# v2.net
KiCad netlist of a schematic drawn in EAGLE
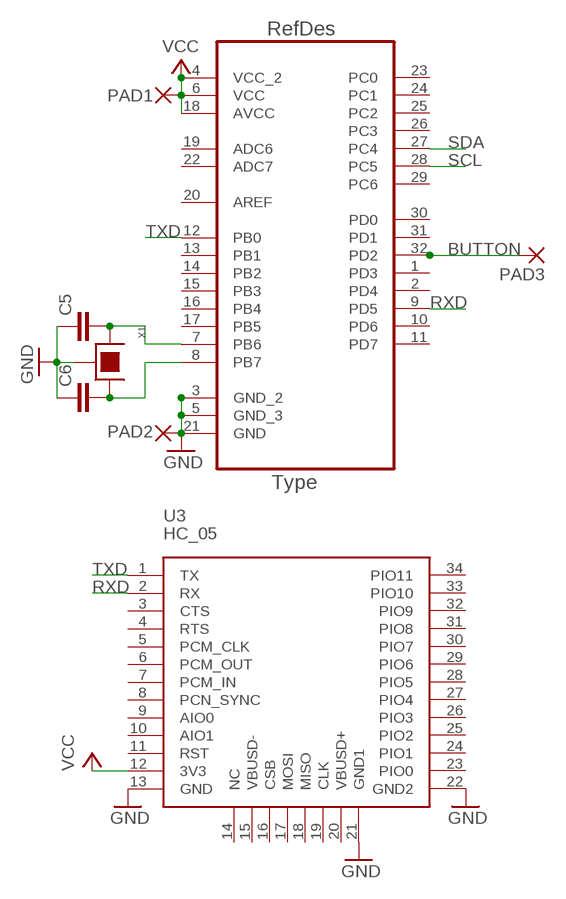
[diagram p0: schematic, sheet 1]
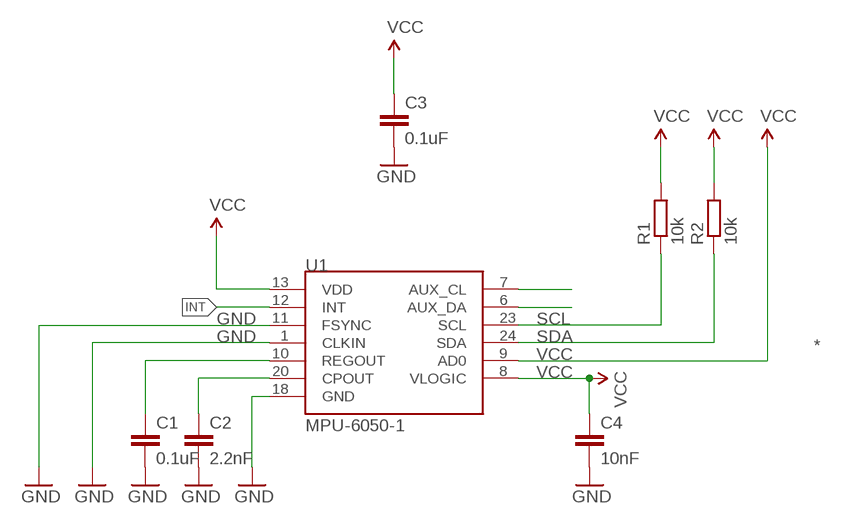
[diagram p1: schematic, sheet 2]

(export (version "E")
  (design (tool "Eeschema 10.0.6"))
  (components
    (comp (ref "C5")
      (value "C-EUC0402")
      (footprint "eagle-import:C0402")
      (libsource (lib "eagle-import") (part "C-EUC0402"))
    )
    (comp (ref "C6")
      (value "C-EUC0402")
      (footprint "eagle-import:C0402")
      (libsource (lib "eagle-import") (part "C-EUC0402"))
    )
    (comp (ref "PAD1")
      (value "SMD2")
      (footprint "eagle-import:SMD1,27-2,54")
      (libsource (lib "eagle-import") (part "SMD2"))
    )
    (comp (ref "PAD2")
      (value "SMD2")
      (footprint "eagle-import:SMD1,27-2,54")
      (libsource (lib "eagle-import") (part "SMD2"))
    )
    (comp (ref "PAD3")
      (value "SMD2")
      (footprint "eagle-import:SMD1,27-2,54")
      (libsource (lib "eagle-import") (part "SMD2"))
    )
    (comp (ref "U2")
      (value "ATMEGA328P-AU")
      (footprint "eagle-import:QFP80P900X900X120-32N")
      (libsource (lib "eagle-import") (part "ATMEGA328P-AU"))
    )
    (comp (ref "U3")
      (value "HC_05")
      (footprint "eagle-import:BLUETOOTH_SMD")
      (libsource (lib "eagle-import") (part "HC_05"))
    )
    (comp (ref "X1")
      (value "SHIELDED_CRYSTAL_TSX-3225")
      (footprint "eagle-import:TSX-3225")
      (libsource (lib "eagle-import") (part "SHIELDED_CRYSTAL_TSX-3225"))
    )
    (comp (ref "C1")
      (value "0.1uF")
      (footprint "eagle-import:C0402")
      (libsource (lib "eagle-import") (part "C-EUC0402"))
    )
    (comp (ref "C2")
      (value "2.2nF")
      (footprint "eagle-import:C0402")
      (libsource (lib "eagle-import") (part "C-EUC0402"))
    )
    (comp (ref "C3")
      (value "0.1uF")
      (footprint "eagle-import:C0402")
      (libsource (lib "eagle-import") (part "C-EUC0402"))
    )
    (comp (ref "C4")
      (value "10nF")
      (footprint "eagle-import:C0402")
      (libsource (lib "eagle-import") (part "C-EUC0402"))
    )
    (comp (ref "R1")
      (value "10k")
      (footprint "eagle-import:R0402")
      (libsource (lib "eagle-import") (part "R-EU_R0402"))
    )
    (comp (ref "R2")
      (value "10k")
      (footprint "eagle-import:R0402")
      (libsource (lib "eagle-import") (part "R-EU_R0402"))
    )
    (comp (ref "U1")
      (value "MPU-6050-1")
      (footprint "eagle-import:QFN-24-4MM2")
      (libsource (lib "eagle-import") (part "MPU-6050-1"))
    )
  )
  (nets
    (net (code "1") (name "BUTTON") (class "Default")
      (node (ref "PAD3") (pin "1") (pinfunction "P_1") (pintype "passive"))
      (node (ref "U2") (pin "32") (pinfunction "PD2_32") (pintype "bidirectional"))
    )
    (net (code "2") (name "GND") (class "Default")
      (node (ref "C1") (pin "2") (pinfunction "2_2") (pintype "passive"))
      (node (ref "C2") (pin "2") (pinfunction "2_2") (pintype "passive"))
      (node (ref "C3") (pin "2") (pinfunction "2_2") (pintype "passive"))
      (node (ref "C4") (pin "2") (pinfunction "2_2") (pintype "passive"))
      (node (ref "C5") (pin "1") (pinfunction "1_1") (pintype "passive"))
      (node (ref "C6") (pin "1") (pinfunction "1_1") (pintype "passive"))
      (node (ref "PAD2") (pin "1") (pinfunction "P_1") (pintype "passive"))
      (node (ref "U1") (pin "1") (pinfunction "CLKIN_1") (pintype "bidirectional"))
      (node (ref "U1") (pin "11") (pinfunction "FSYNC_11") (pintype "bidirectional"))
      (node (ref "U1") (pin "18") (pinfunction "GND_18") (pintype "bidirectional"))
      (node (ref "U2") (pin "21") (pinfunction "GND_21") (pintype "passive"))
      (node (ref "U2") (pin "3") (pinfunction "GND_2_3") (pintype "passive"))
      (node (ref "U2") (pin "5") (pinfunction "GND_3_5") (pintype "passive"))
      (node (ref "U3") (pin "13") (pinfunction "GND_13") (pintype "bidirectional"))
      (node (ref "U3") (pin "21") (pinfunction "GND1_21") (pintype "bidirectional"))
      (node (ref "U3") (pin "22") (pinfunction "GND2_22") (pintype "bidirectional"))
      (node (ref "X1") (pin "2") (pinfunction "P$3_2") (pintype "bidirectional"))
      (node (ref "X1") (pin "4") (pinfunction "P$3_4") (pintype "bidirectional"))
    )
    (net (code "3") (name "INT") (class "Default")
      (node (ref "U1") (pin "12") (pinfunction "INT_12") (pintype "bidirectional"))
    )
    (net (code "4") (name "Net-(U1-CPOUT)") (class "Default")
      (node (ref "C2") (pin "1") (pinfunction "1_1") (pintype "passive"))
      (node (ref "U1") (pin "20") (pinfunction "CPOUT_20") (pintype "bidirectional"))
    )
    (net (code "5") (name "Net-(U1-REGOUT)") (class "Default")
      (node (ref "C1") (pin "1") (pinfunction "1_1") (pintype "passive"))
      (node (ref "U1") (pin "10") (pinfunction "REGOUT_10") (pintype "bidirectional"))
    )
    (net (code "6") (name "Net-(U2-PB6)") (class "Default")
      (node (ref "C5") (pin "2") (pinfunction "2_2") (pintype "passive"))
      (node (ref "U2") (pin "7") (pinfunction "PB6_7") (pintype "bidirectional"))
      (node (ref "X1") (pin "1") (pinfunction "P$1_1") (pintype "bidirectional"))
    )
    (net (code "7") (name "Net-(U2-PB7)") (class "Default")
      (node (ref "C6") (pin "2") (pinfunction "2_2") (pintype "passive"))
      (node (ref "U2") (pin "8") (pinfunction "PB7_8") (pintype "bidirectional"))
      (node (ref "X1") (pin "3") (pinfunction "P$2_3") (pintype "bidirectional"))
    )
    (net (code "8") (name "RXD") (class "Default")
      (node (ref "U2") (pin "9") (pinfunction "PD5_9") (pintype "bidirectional"))
      (node (ref "U3") (pin "2") (pinfunction "RX_2") (pintype "bidirectional"))
    )
    (net (code "9") (name "SCL") (class "Default")
      (node (ref "R1") (pin "1") (pinfunction "1_1") (pintype "passive"))
      (node (ref "U1") (pin "23") (pinfunction "SCL_23") (pintype "bidirectional"))
      (node (ref "U2") (pin "28") (pinfunction "PC5_28") (pintype "bidirectional"))
    )
    (net (code "10") (name "SDA") (class "Default")
      (node (ref "R2") (pin "1") (pinfunction "1_1") (pintype "passive"))
      (node (ref "U1") (pin "24") (pinfunction "SDA_24") (pintype "bidirectional"))
      (node (ref "U2") (pin "27") (pinfunction "PC4_27") (pintype "bidirectional"))
    )
    (net (code "11") (name "TXD") (class "Default")
      (node (ref "U2") (pin "12") (pinfunction "PB0_12") (pintype "bidirectional"))
      (node (ref "U3") (pin "1") (pinfunction "TX_1") (pintype "bidirectional"))
    )
    (net (code "12") (name "VCC") (class "Default")
      (node (ref "C3") (pin "1") (pinfunction "1_1") (pintype "passive"))
      (node (ref "C4") (pin "1") (pinfunction "1_1") (pintype "passive"))
      (node (ref "PAD1") (pin "1") (pinfunction "P_1") (pintype "passive"))
      (node (ref "R1") (pin "2") (pinfunction "2_2") (pintype "passive"))
      (node (ref "R2") (pin "2") (pinfunction "2_2") (pintype "passive"))
      (node (ref "U1") (pin "13") (pinfunction "VDD_13") (pintype "bidirectional"))
      (node (ref "U1") (pin "8") (pinfunction "VLOGIC_8") (pintype "bidirectional"))
      (node (ref "U1") (pin "9") (pinfunction "AD0_9") (pintype "bidirectional"))
      (node (ref "U2") (pin "18") (pinfunction "AVCC_18") (pintype "power_in"))
      (node (ref "U2") (pin "4") (pinfunction "VCC_2_4") (pintype "power_in"))
      (node (ref "U2") (pin "6") (pinfunction "VCC_6") (pintype "power_in"))
      (node (ref "U3") (pin "12") (pinfunction "3V3_12") (pintype "bidirectional"))
    )
    (net (code "13") (name "unconnected-(U1-AUX_CL-Pad7)") (class "Default")
      (node (ref "U1") (pin "7") (pinfunction "AUX_CL_7") (pintype "bidirectional"))
    )
    (net (code "14") (name "unconnected-(U1-AUX_DA-Pad6)") (class "Default")
      (node (ref "U1") (pin "6") (pinfunction "AUX_DA_6") (pintype "bidirectional"))
    )
    (net (code "15") (name "unconnected-(U2-ADC6-Pad19)") (class "Default")
      (node (ref "U2") (pin "19") (pinfunction "ADC6_19") (pintype "input"))
    )
    (net (code "16") (name "unconnected-(U2-ADC7-Pad22)") (class "Default")
      (node (ref "U2") (pin "22") (pinfunction "ADC7_22") (pintype "input"))
    )
    (net (code "17") (name "unconnected-(U2-AREF-Pad20)") (class "Default")
      (node (ref "U2") (pin "20") (pinfunction "AREF_20") (pintype "input"))
    )
    (net (code "18") (name "unconnected-(U2-PB1-Pad13)") (class "Default")
      (node (ref "U2") (pin "13") (pinfunction "PB1_13") (pintype "bidirectional"))
    )
    (net (code "19") (name "unconnected-(U2-PB2-Pad14)") (class "Default")
      (node (ref "U2") (pin "14") (pinfunction "PB2_14") (pintype "bidirectional"))
    )
    (net (code "20") (name "unconnected-(U2-PB3-Pad15)") (class "Default")
      (node (ref "U2") (pin "15") (pinfunction "PB3_15") (pintype "bidirectional"))
    )
    (net (code "21") (name "unconnected-(U2-PB4-Pad16)") (class "Default")
      (node (ref "U2") (pin "16") (pinfunction "PB4_16") (pintype "bidirectional"))
    )
    (net (code "22") (name "unconnected-(U2-PB5-Pad17)") (class "Default")
      (node (ref "U2") (pin "17") (pinfunction "PB5_17") (pintype "bidirectional"))
    )
    (net (code "23") (name "unconnected-(U2-PC0-Pad23)") (class "Default")
      (node (ref "U2") (pin "23") (pinfunction "PC0_23") (pintype "bidirectional"))
    )
    (net (code "24") (name "unconnected-(U2-PC1-Pad24)") (class "Default")
      (node (ref "U2") (pin "24") (pinfunction "PC1_24") (pintype "bidirectional"))
    )
    (net (code "25") (name "unconnected-(U2-PC2-Pad25)") (class "Default")
      (node (ref "U2") (pin "25") (pinfunction "PC2_25") (pintype "bidirectional"))
    )
    (net (code "26") (name "unconnected-(U2-PC3-Pad26)") (class "Default")
      (node (ref "U2") (pin "26") (pinfunction "PC3_26") (pintype "bidirectional"))
    )
    (net (code "27") (name "unconnected-(U2-PC6-Pad29)") (class "Default")
      (node (ref "U2") (pin "29") (pinfunction "PC6_29") (pintype "bidirectional"))
    )
    (net (code "28") (name "unconnected-(U2-PD0-Pad30)") (class "Default")
      (node (ref "U2") (pin "30") (pinfunction "PD0_30") (pintype "bidirectional"))
    )
    (net (code "29") (name "unconnected-(U2-PD1-Pad31)") (class "Default")
      (node (ref "U2") (pin "31") (pinfunction "PD1_31") (pintype "bidirectional"))
    )
    (net (code "30") (name "unconnected-(U2-PD3-Pad1)") (class "Default")
      (node (ref "U2") (pin "1") (pinfunction "PD3_1") (pintype "bidirectional"))
    )
    (net (code "31") (name "unconnected-(U2-PD4-Pad2)") (class "Default")
      (node (ref "U2") (pin "2") (pinfunction "PD4_2") (pintype "bidirectional"))
    )
    (net (code "32") (name "unconnected-(U2-PD6-Pad10)") (class "Default")
      (node (ref "U2") (pin "10") (pinfunction "PD6_10") (pintype "bidirectional"))
    )
    (net (code "33") (name "unconnected-(U2-PD7-Pad11)") (class "Default")
      (node (ref "U2") (pin "11") (pinfunction "PD7_11") (pintype "bidirectional"))
    )
    (net (code "34") (name "unconnected-(U3-AIO0-Pad9)") (class "Default")
      (node (ref "U3") (pin "9") (pinfunction "AIO0_9") (pintype "bidirectional"))
    )
    (net (code "35") (name "unconnected-(U3-AIO1-Pad10)") (class "Default")
      (node (ref "U3") (pin "10") (pinfunction "AIO1_10") (pintype "bidirectional"))
    )
    (net (code "36") (name "unconnected-(U3-CLK-Pad19)") (class "Default")
      (node (ref "U3") (pin "19") (pinfunction "CLK_19") (pintype "bidirectional"))
    )
    (net (code "37") (name "unconnected-(U3-CSB-Pad16)") (class "Default")
      (node (ref "U3") (pin "16") (pinfunction "CSB_16") (pintype "bidirectional"))
    )
    (net (code "38") (name "unconnected-(U3-CTS-Pad3)") (class "Default")
      (node (ref "U3") (pin "3") (pinfunction "CTS_3") (pintype "bidirectional"))
    )
    (net (code "39") (name "unconnected-(U3-MISO-Pad18)") (class "Default")
      (node (ref "U3") (pin "18") (pinfunction "MISO_18") (pintype "bidirectional"))
    )
    (net (code "40") (name "unconnected-(U3-MOSI-Pad17)") (class "Default")
      (node (ref "U3") (pin "17") (pinfunction "MOSI_17") (pintype "bidirectional"))
    )
    (net (code "41") (name "unconnected-(U3-NC-Pad14)") (class "Default")
      (node (ref "U3") (pin "14") (pinfunction "NC_14") (pintype "bidirectional"))
    )
    (net (code "42") (name "unconnected-(U3-PCM_CLK-Pad5)") (class "Default")
      (node (ref "U3") (pin "5") (pinfunction "PCM_CLK_5") (pintype "bidirectional"))
    )
    (net (code "43") (name "unconnected-(U3-PCM_IN-Pad7)") (class "Default")
      (node (ref "U3") (pin "7") (pinfunction "PCM_IN_7") (pintype "bidirectional"))
    )
    (net (code "44") (name "unconnected-(U3-PCM_OUT-Pad6)") (class "Default")
      (node (ref "U3") (pin "6") (pinfunction "PCM_OUT_6") (pintype "bidirectional"))
    )
    (net (code "45") (name "unconnected-(U3-PCN_SYNC-Pad8)") (class "Default")
      (node (ref "U3") (pin "8") (pinfunction "PCN_SYNC_8") (pintype "bidirectional"))
    )
    (net (code "46") (name "unconnected-(U3-PIO0-Pad23)") (class "Default")
      (node (ref "U3") (pin "23") (pinfunction "PIO0_23") (pintype "bidirectional"))
    )
    (net (code "47") (name "unconnected-(U3-PIO1-Pad24)") (class "Default")
      (node (ref "U3") (pin "24") (pinfunction "PIO1_24") (pintype "bidirectional"))
    )
    (net (code "48") (name "unconnected-(U3-PIO2-Pad25)") (class "Default")
      (node (ref "U3") (pin "25") (pinfunction "PIO2_25") (pintype "bidirectional"))
    )
    (net (code "49") (name "unconnected-(U3-PIO3-Pad26)") (class "Default")
      (node (ref "U3") (pin "26") (pinfunction "PIO3_26") (pintype "bidirectional"))
    )
    (net (code "50") (name "unconnected-(U3-PIO4-Pad27)") (class "Default")
      (node (ref "U3") (pin "27") (pinfunction "PIO4_27") (pintype "bidirectional"))
    )
    (net (code "51") (name "unconnected-(U3-PIO5-Pad28)") (class "Default")
      (node (ref "U3") (pin "28") (pinfunction "PIO5_28") (pintype "bidirectional"))
    )
    (net (code "52") (name "unconnected-(U3-PIO6-Pad29)") (class "Default")
      (node (ref "U3") (pin "29") (pinfunction "PIO6_29") (pintype "bidirectional"))
    )
    (net (code "53") (name "unconnected-(U3-PIO7-Pad30)") (class "Default")
      (node (ref "U3") (pin "30") (pinfunction "PIO7_30") (pintype "bidirectional"))
    )
    (net (code "54") (name "unconnected-(U3-PIO8-Pad31)") (class "Default")
      (node (ref "U3") (pin "31") (pinfunction "PIO8_31") (pintype "bidirectional"))
    )
    (net (code "55") (name "unconnected-(U3-PIO9-Pad32)") (class "Default")
      (node (ref "U3") (pin "32") (pinfunction "PIO9_32") (pintype "bidirectional"))
    )
    (net (code "56") (name "unconnected-(U3-PIO10-Pad33)") (class "Default")
      (node (ref "U3") (pin "33") (pinfunction "PIO10_33") (pintype "bidirectional"))
    )
    (net (code "57") (name "unconnected-(U3-PIO11-Pad34)") (class "Default")
      (node (ref "U3") (pin "34") (pinfunction "PIO11_34") (pintype "bidirectional"))
    )
    (net (code "58") (name "unconnected-(U3-RST-Pad11)") (class "Default")
      (node (ref "U3") (pin "11") (pinfunction "RST_11") (pintype "bidirectional"))
    )
    (net (code "59") (name "unconnected-(U3-RTS-Pad4)") (class "Default")
      (node (ref "U3") (pin "4") (pinfunction "RTS_4") (pintype "bidirectional"))
    )
    (net (code "60") (name "unconnected-(U3-VBUSD+-Pad20)") (class "Default")
      (node (ref "U3") (pin "20") (pinfunction "VBUSD+_20") (pintype "bidirectional"))
    )
    (net (code "61") (name "unconnected-(U3-VBUSD--Pad15)") (class "Default")
      (node (ref "U3") (pin "15") (pinfunction "VBUSD-_15") (pintype "bidirectional"))
    )
  )
)
